# MCU.net
KiCad netlist of a schematic drawn in Altium Designer
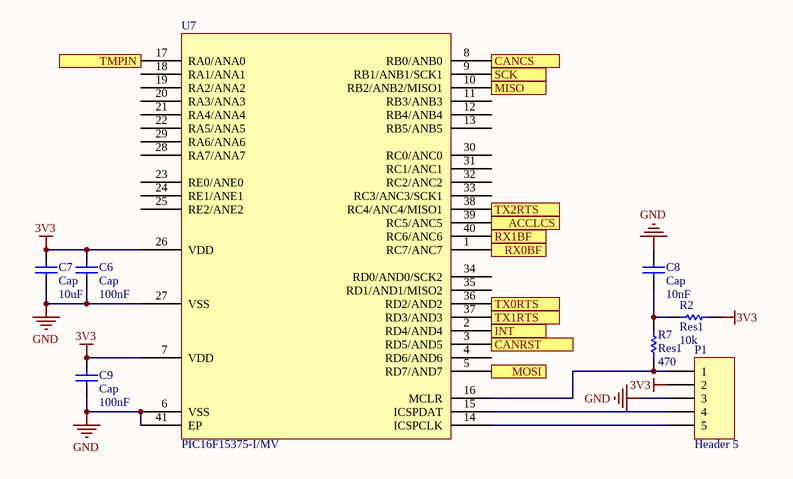
[diagram p0: MCU.SchDoc]

(export (version "E")
  (design (tool "Eeschema 10.0.6"))
  (components
    (comp (ref "C6")
      (value "Cap")
      (footprint "1608[0603]")
      (description "Capacitor")
      (fields (field (name "ALTIUM_VALUE") "100nF") (field (name "PUBLISHER") "Altium Limited"))
      (libsource (lib "Miscellaneous Devices") (part "Cap"))
    )
    (comp (ref "C7")
      (value "Cap")
      (footprint "6-0805_M")
      (description "Capacitor")
      (fields (field (name "ALTIUM_VALUE") "10uF") (field (name "PUBLISHER") "Altium Limited"))
      (libsource (lib "Miscellaneous Devices") (part "Cap"))
    )
    (comp (ref "C8")
      (value "Cap")
      (footprint "1608[0603]")
      (description "Capacitor")
      (fields (field (name "ALTIUM_VALUE") "10nF") (field (name "PUBLISHER") "Altium Limited"))
      (libsource (lib "Miscellaneous Devices") (part "Cap"))
    )
    (comp (ref "C9")
      (value "Cap")
      (footprint "1608[0603]")
      (description "Capacitor")
      (fields (field (name "ALTIUM_VALUE") "100nF") (field (name "PUBLISHER") "Altium Limited"))
      (libsource (lib "Miscellaneous Devices") (part "Cap"))
    )
    (comp (ref "P1")
      (value "Header 5")
      (footprint "HDR1X5")
      (description "Header, 5-Pin")
      (fields (field (name "PUBLISHER") "Altium Limited"))
      (libsource (lib "Miscellaneous Connectors") (part "Header 5"))
    )
    (comp (ref "R2")
      (value "Res1")
      (footprint "0402-A")
      (description "Resistor")
      (fields (field (name "ALTIUM_VALUE") "10k") (field (name "PUBLISHER") "Altium Limited"))
      (libsource (lib "Miscellaneous Devices") (part "Res1"))
    )
    (comp (ref "R7")
      (value "Res1")
      (footprint "0402-A")
      (description "Resistor")
      (fields (field (name "ALTIUM_VALUE") "470") (field (name "PUBLISHER") "Altium Limited"))
      (libsource (lib "Miscellaneous Devices") (part "Res1"))
    )
    (comp (ref "U7")
      (value "PIC16F15375-I/MV")
      (footprint "PIC16F15375-I/MV")
      (libsource (lib "PIC16F15375") (part "PIC16F15375-I/MV"))
    )
  )
  (nets
    (net (code "1") (name "/ACCLCS") (class "Default")
      (node (ref "U7") (pin "39") (pinfunction "RC5/ANC5_39") (pintype "passive"))
    )
    (net (code "2") (name "/CANCS") (class "Default")
      (node (ref "U7") (pin "8") (pinfunction "RB0/ANB0_8") (pintype "passive"))
    )
    (net (code "3") (name "/CANRST") (class "Default")
      (node (ref "U7") (pin "3") (pinfunction "RD5/AND5_3") (pintype "passive"))
    )
    (net (code "4") (name "/INT") (class "Default")
      (node (ref "U7") (pin "2") (pinfunction "RD4/AND4_2") (pintype "passive"))
    )
    (net (code "5") (name "/MISO") (class "Default")
      (node (ref "U7") (pin "10") (pinfunction "RB2/ANB2/MISO1_10") (pintype "passive"))
    )
    (net (code "6") (name "/MOSI") (class "Default")
      (node (ref "U7") (pin "5") (pinfunction "RD7/AND7_5") (pintype "passive"))
    )
    (net (code "7") (name "/RX0BF") (class "Default")
      (node (ref "U7") (pin "1") (pinfunction "RC7/ANC7_1") (pintype "passive"))
    )
    (net (code "8") (name "/RX1BF") (class "Default")
      (node (ref "U7") (pin "40") (pinfunction "RC6/ANC6_40") (pintype "passive"))
    )
    (net (code "9") (name "/SCK") (class "Default")
      (node (ref "U7") (pin "9") (pinfunction "RB1/ANB1/SCK1_9") (pintype "passive"))
    )
    (net (code "10") (name "/TMPIN") (class "Default")
      (node (ref "U7") (pin "17") (pinfunction "RA0/ANA0_17") (pintype "passive"))
    )
    (net (code "11") (name "/TX0RTS") (class "Default")
      (node (ref "U7") (pin "36") (pinfunction "RD2/AND2_36") (pintype "passive"))
    )
    (net (code "12") (name "/TX1RTS") (class "Default")
      (node (ref "U7") (pin "37") (pinfunction "RD3/AND3_37") (pintype "passive"))
    )
    (net (code "13") (name "/TX2RTS") (class "Default")
      (node (ref "U7") (pin "38") (pinfunction "RC4/ANC4/MISO1_38") (pintype "passive"))
    )
    (net (code "14") (name "3V3") (class "Default")
      (node (ref "C6") (pin "2") (pinfunction "2_2") (pintype "passive"))
      (node (ref "C7") (pin "2") (pinfunction "2_2") (pintype "passive"))
      (node (ref "C9") (pin "2") (pinfunction "2_2") (pintype "passive"))
      (node (ref "P1") (pin "2") (pinfunction "2_2") (pintype "passive"))
      (node (ref "R2") (pin "2") (pinfunction "2_2") (pintype "passive"))
      (node (ref "U7") (pin "26") (pinfunction "VDD_26") (pintype "passive"))
      (node (ref "U7") (pin "7") (pinfunction "VDD_7") (pintype "passive"))
    )
    (net (code "15") (name "GND") (class "Default")
      (node (ref "C6") (pin "1") (pinfunction "1_1") (pintype "passive"))
      (node (ref "C7") (pin "1") (pinfunction "1_1") (pintype "passive"))
      (node (ref "C8") (pin "1") (pinfunction "1_1") (pintype "passive"))
      (node (ref "C9") (pin "1") (pinfunction "1_1") (pintype "passive"))
      (node (ref "P1") (pin "3") (pinfunction "3_3") (pintype "passive"))
      (node (ref "U7") (pin "27") (pinfunction "VSS_27") (pintype "passive"))
      (node (ref "U7") (pin "41") (pinfunction "EP_41") (pintype "power_in"))
      (node (ref "U7") (pin "6") (pinfunction "VSS_6") (pintype "passive"))
    )
    (net (code "16") (name "Net-(C8-Pad2)") (class "Default")
      (node (ref "C8") (pin "2") (pinfunction "2_2") (pintype "passive"))
      (node (ref "R2") (pin "1") (pinfunction "1_1") (pintype "passive"))
      (node (ref "R7") (pin "2") (pinfunction "2_2") (pintype "passive"))
    )
    (net (code "17") (name "Net-(U7-ICSPCLK)") (class "Default")
      (node (ref "P1") (pin "5") (pinfunction "5_5") (pintype "passive"))
      (node (ref "U7") (pin "14") (pinfunction "ICSPCLK_14") (pintype "passive"))
    )
    (net (code "18") (name "Net-(U7-ICSPDAT)") (class "Default")
      (node (ref "P1") (pin "4") (pinfunction "4_4") (pintype "passive"))
      (node (ref "U7") (pin "15") (pinfunction "ICSPDAT_15") (pintype "passive"))
    )
    (net (code "19") (name "Net-(U7-MCLR)") (class "Default")
      (node (ref "P1") (pin "1") (pinfunction "1_1") (pintype "passive"))
      (node (ref "R7") (pin "1") (pinfunction "1_1") (pintype "passive"))
      (node (ref "U7") (pin "16") (pinfunction "MCLR_16") (pintype "passive"))
    )
    (net (code "20") (name "unconnected-(U7-RA1{slash}ANA1-Pad18)") (class "Default")
      (node (ref "U7") (pin "18") (pinfunction "RA1/ANA1_18") (pintype "passive"))
    )
    (net (code "21") (name "unconnected-(U7-RA2{slash}ANA2-Pad19)") (class "Default")
      (node (ref "U7") (pin "19") (pinfunction "RA2/ANA2_19") (pintype "passive"))
    )
    (net (code "22") (name "unconnected-(U7-RA3{slash}ANA3-Pad20)") (class "Default")
      (node (ref "U7") (pin "20") (pinfunction "RA3/ANA3_20") (pintype "passive"))
    )
    (net (code "23") (name "unconnected-(U7-RA4{slash}ANA4-Pad21)") (class "Default")
      (node (ref "U7") (pin "21") (pinfunction "RA4/ANA4_21") (pintype "passive"))
    )
    (net (code "24") (name "unconnected-(U7-RA5{slash}ANA5-Pad22)") (class "Default")
      (node (ref "U7") (pin "22") (pinfunction "RA5/ANA5_22") (pintype "passive"))
    )
    (net (code "25") (name "unconnected-(U7-RA6{slash}ANA6-Pad29)") (class "Default")
      (node (ref "U7") (pin "29") (pinfunction "RA6/ANA6_29") (pintype "passive"))
    )
    (net (code "26") (name "unconnected-(U7-RA7{slash}ANA7-Pad28)") (class "Default")
      (node (ref "U7") (pin "28") (pinfunction "RA7/ANA7_28") (pintype "passive"))
    )
    (net (code "27") (name "unconnected-(U7-RB3{slash}ANB3-Pad11)") (class "Default")
      (node (ref "U7") (pin "11") (pinfunction "RB3/ANB3_11") (pintype "passive"))
    )
    (net (code "28") (name "unconnected-(U7-RB4{slash}ANB4-Pad12)") (class "Default")
      (node (ref "U7") (pin "12") (pinfunction "RB4/ANB4_12") (pintype "passive"))
    )
    (net (code "29") (name "unconnected-(U7-RB5{slash}ANB5-Pad13)") (class "Default")
      (node (ref "U7") (pin "13") (pinfunction "RB5/ANB5_13") (pintype "passive"))
    )
    (net (code "30") (name "unconnected-(U7-RC0{slash}ANC0-Pad30)") (class "Default")
      (node (ref "U7") (pin "30") (pinfunction "RC0/ANC0_30") (pintype "passive"))
    )
    (net (code "31") (name "unconnected-(U7-RC1{slash}ANC1-Pad31)") (class "Default")
      (node (ref "U7") (pin "31") (pinfunction "RC1/ANC1_31") (pintype "passive"))
    )
    (net (code "32") (name "unconnected-(U7-RC2{slash}ANC2-Pad32)") (class "Default")
      (node (ref "U7") (pin "32") (pinfunction "RC2/ANC2_32") (pintype "passive"))
    )
    (net (code "33") (name "unconnected-(U7-RC3{slash}ANC3{slash}SCK1-Pad33)") (class "Default")
      (node (ref "U7") (pin "33") (pinfunction "RC3/ANC3/SCK1_33") (pintype "passive"))
    )
    (net (code "34") (name "unconnected-(U7-RD0{slash}AND0{slash}SCK2-Pad34)") (class "Default")
      (node (ref "U7") (pin "34") (pinfunction "RD0/AND0/SCK2_34") (pintype "passive"))
    )
    (net (code "35") (name "unconnected-(U7-RD1{slash}AND1{slash}MISO2-Pad35)") (class "Default")
      (node (ref "U7") (pin "35") (pinfunction "RD1/AND1/MISO2_35") (pintype "passive"))
    )
    (net (code "36") (name "unconnected-(U7-RD6{slash}AND6-Pad4)") (class "Default")
      (node (ref "U7") (pin "4") (pinfunction "RD6/AND6_4") (pintype "passive"))
    )
    (net (code "37") (name "unconnected-(U7-RE0{slash}ANE0-Pad23)") (class "Default")
      (node (ref "U7") (pin "23") (pinfunction "RE0/ANE0_23") (pintype "passive"))
    )
    (net (code "38") (name "unconnected-(U7-RE1{slash}ANE1-Pad24)") (class "Default")
      (node (ref "U7") (pin "24") (pinfunction "RE1/ANE1_24") (pintype "passive"))
    )
    (net (code "39") (name "unconnected-(U7-RE2{slash}ANE2-Pad25)") (class "Default")
      (node (ref "U7") (pin "25") (pinfunction "RE2/ANE2_25") (pintype "passive"))
    )
  )
)
